# SunS_fixture_EGSE_Top.net
KiCad netlist of a schematic drawn in Altium Designer
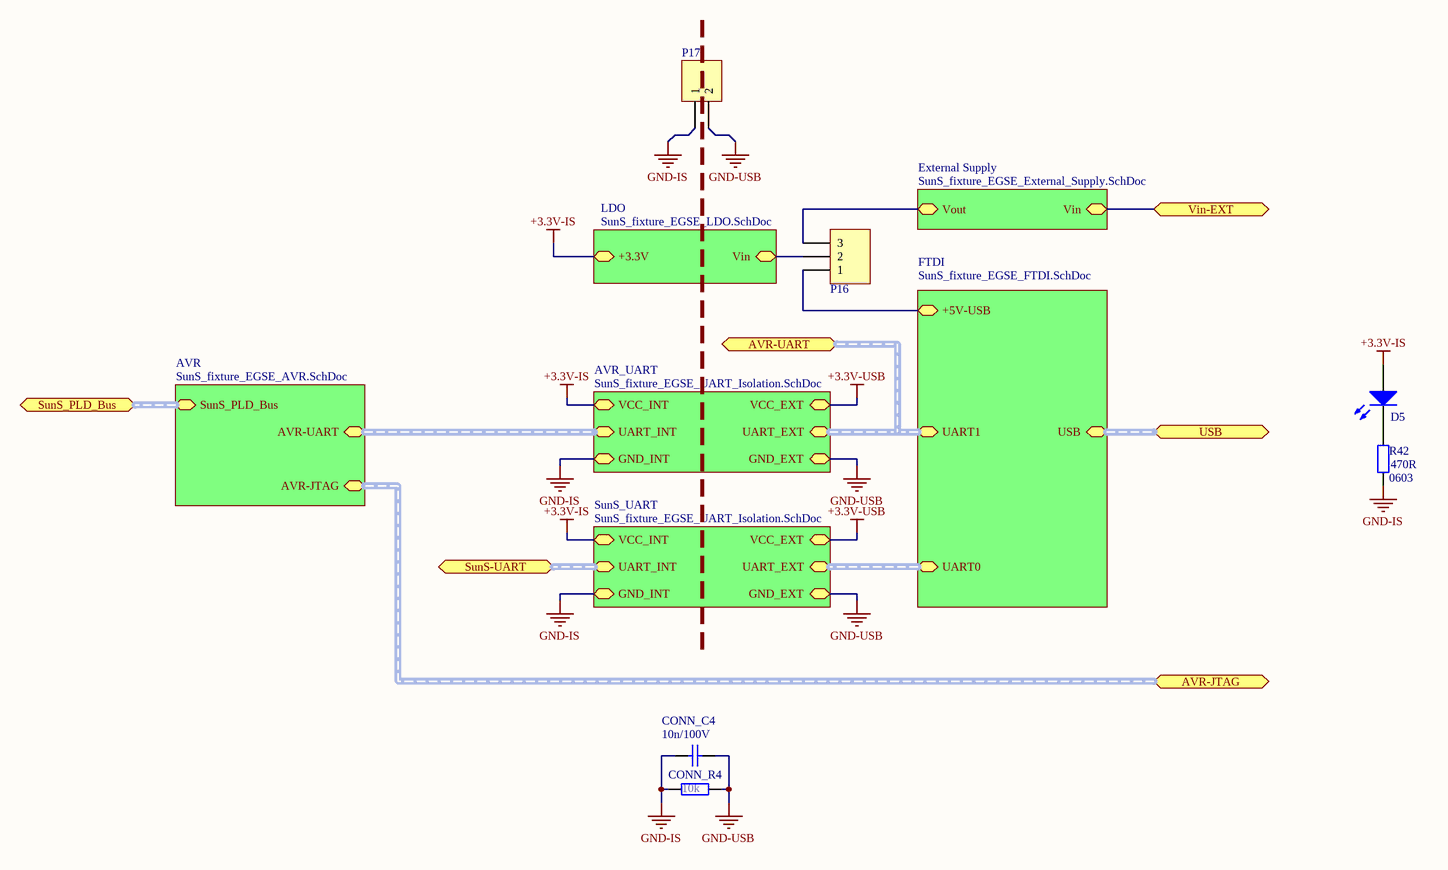
[diagram p0: SunS_fixture_EGSE_Top.SchDoc]

(export (version "E")
  (design (tool "Eeschema 10.0.6"))
  (components
    (comp (ref "CONN_C4")
      (value "10n/100V")
      (footprint "SMD_Capacitor_0805")
      (description "Ceramic Cap Kemet COTS 100n/100V X7R 0805")
      (fields
        (field (name "MANUFACTURERPARTNUMBER") "C0805T104K1RCLTU")
        (field (name "MANUFACTURER") "Kemet")
      )
      (libsource (lib "capacitors") (part "Cer_C0805T104K1RCLTU"))
    )
    (comp (ref "CONN_R4")
      (value "10k")
      (footprint "SMD_Resistor_0805")
      (description "1k/1% Vishay CRCW 0805 Resistor. 125mW, 100ppm, 150V.")
      (fields
        (field (name "MANUFACTURER") "Vishay")
        (field (name "MANUFACTURERPARTNUMBER") "CRCW08051K00FKxxxx")
      )
      (libsource (lib "resistors") (part "CRCW08051K00FKxxxx"))
    )
    (comp (ref "D5")
      (value "LEDX")
      (footprint "LED 0805 RED")
      (description "Typical LED")
      (libsource (lib "diodes") (part "LEDX"))
    )
    (comp (ref "P16")
      (value "Header 3")
      (footprint "HEADER 1X3 MALE")
      (description "Header, 3-Pin")
      (fields (field (name "PUBLISHER") "Altium Limited"))
      (libsource (lib "connectors_printed-circuit-board") (part "Header 3"))
    )
    (comp (ref "P17")
      (value "Header 2")
      (footprint "HEADER 1X2 Male")
      (description "Header, 2-Pin")
      (fields (field (name "PUBLISHER") "Altium Limited"))
      (libsource (lib "connectors_printed-circuit-board") (part "Header 2"))
    )
    (comp (ref "R42")
      (value "470R")
      (footprint "SMD_Resistor_0603")
      (fields (field (name "PACKAGE") "0603"))
      (libsource (lib "resistors") (part "Res"))
    )
  )
  (nets
    (net (code "6") (name "+3.3V-IS") (class "Default")
      (node (ref "D5") (pin "1") (pinfunction "A_1") (pintype "passive"))
    )
    (net (code "8") (name "/+5V-USB") (class "Default")
      (node (ref "P16") (pin "1") (pinfunction "1_1") (pintype "passive"))
    )
    (net (code "16") (name "/Vin") (class "Default")
      (node (ref "P16") (pin "2") (pinfunction "2_2") (pintype "passive"))
    )
    (net (code "18") (name "/Vout") (class "Default")
      (node (ref "P16") (pin "3") (pinfunction "3_3") (pintype "passive"))
    )
    (net (code "19") (name "GND-IS") (class "Default")
      (node (ref "CONN_C4") (pin "1") (pinfunction "1_1") (pintype "passive"))
      (node (ref "CONN_R4") (pin "1") (pinfunction "1_1") (pintype "passive"))
      (node (ref "P17") (pin "1") (pinfunction "1_1") (pintype "passive"))
      (node (ref "R42") (pin "1") (pinfunction "1_1") (pintype "passive"))
    )
    (net (code "20") (name "GND-USB") (class "Default")
      (node (ref "CONN_C4") (pin "2") (pinfunction "2_2") (pintype "passive"))
      (node (ref "CONN_R4") (pin "2") (pinfunction "2_2") (pintype "passive"))
      (node (ref "P17") (pin "2") (pinfunction "2_2") (pintype "passive"))
    )
    (net (code "21") (name "Net-(D5-K)") (class "Default")
      (node (ref "D5") (pin "2") (pinfunction "K_2") (pintype "passive"))
      (node (ref "R42") (pin "2") (pinfunction "2_2") (pintype "passive"))
    )
  )
)
